# 1_Power.net
KiCad netlist of a schematic drawn in Altium Designer
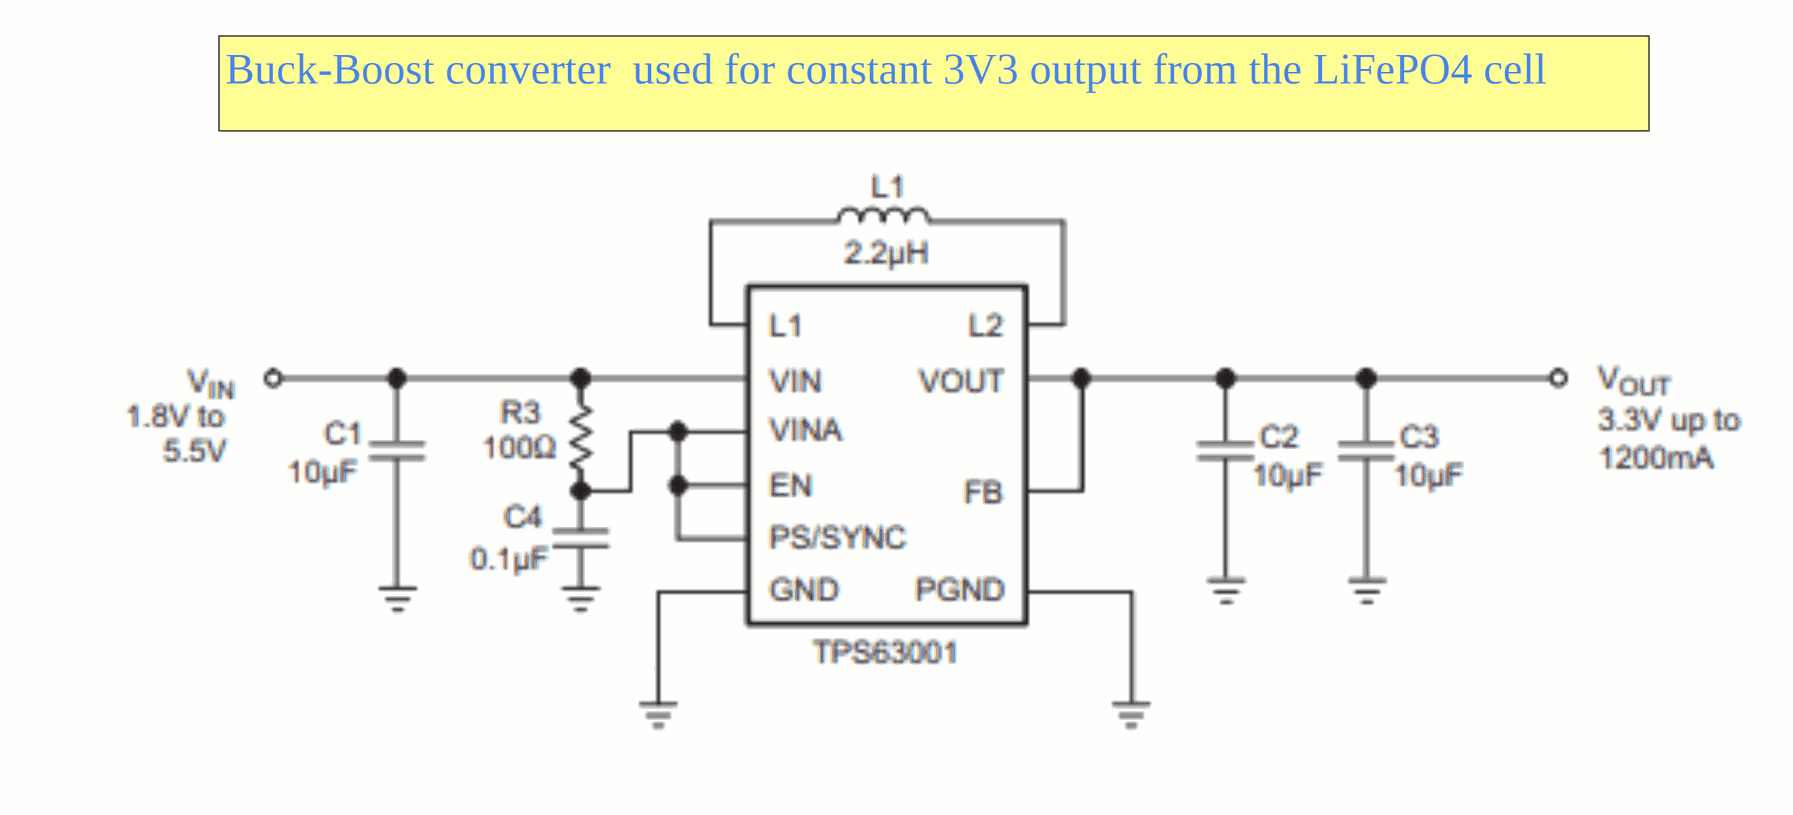
[diagram p0: 1_Power.SchDoc, top left]
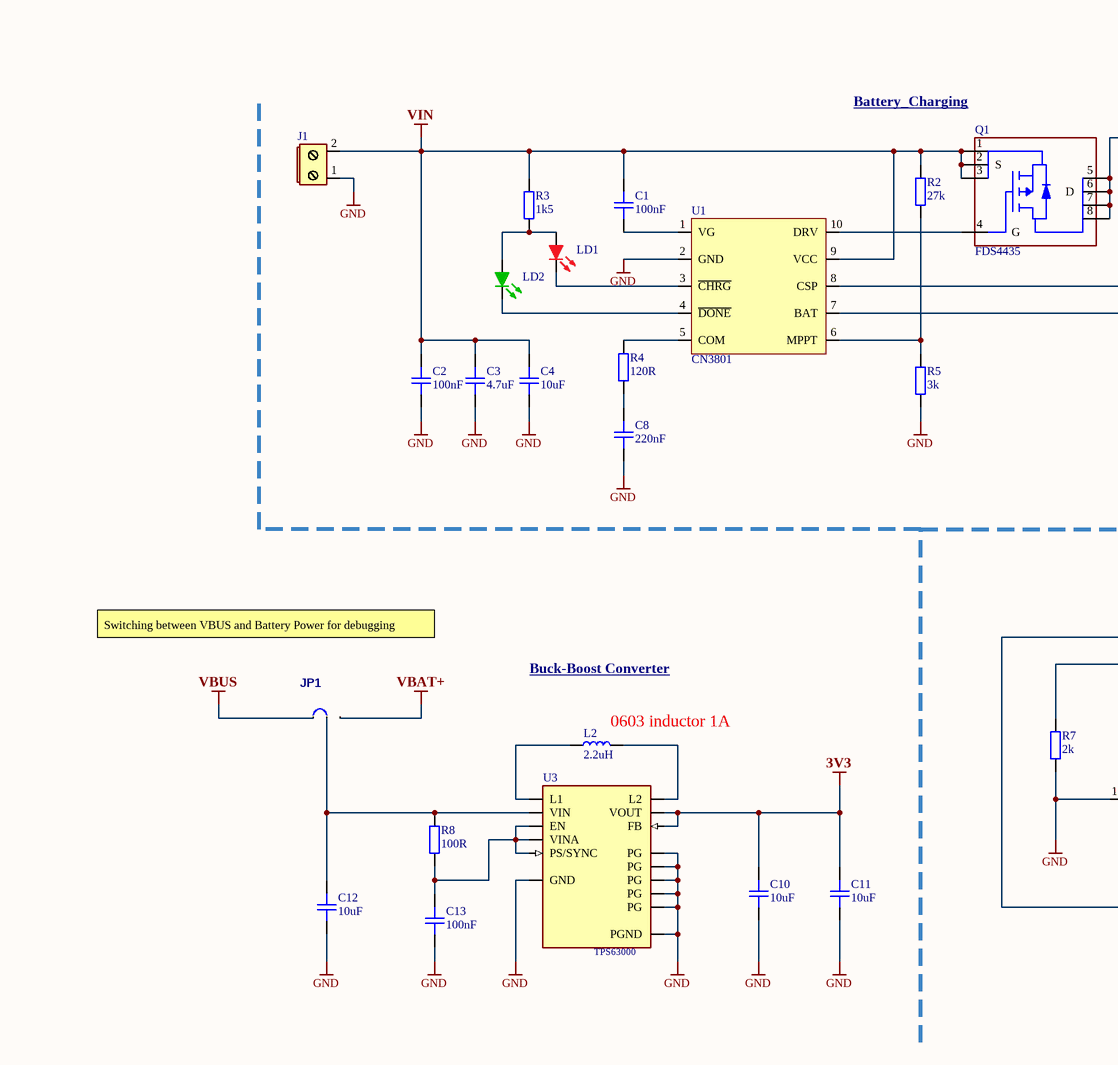
[diagram p1: 1_Power.SchDoc, top middle]
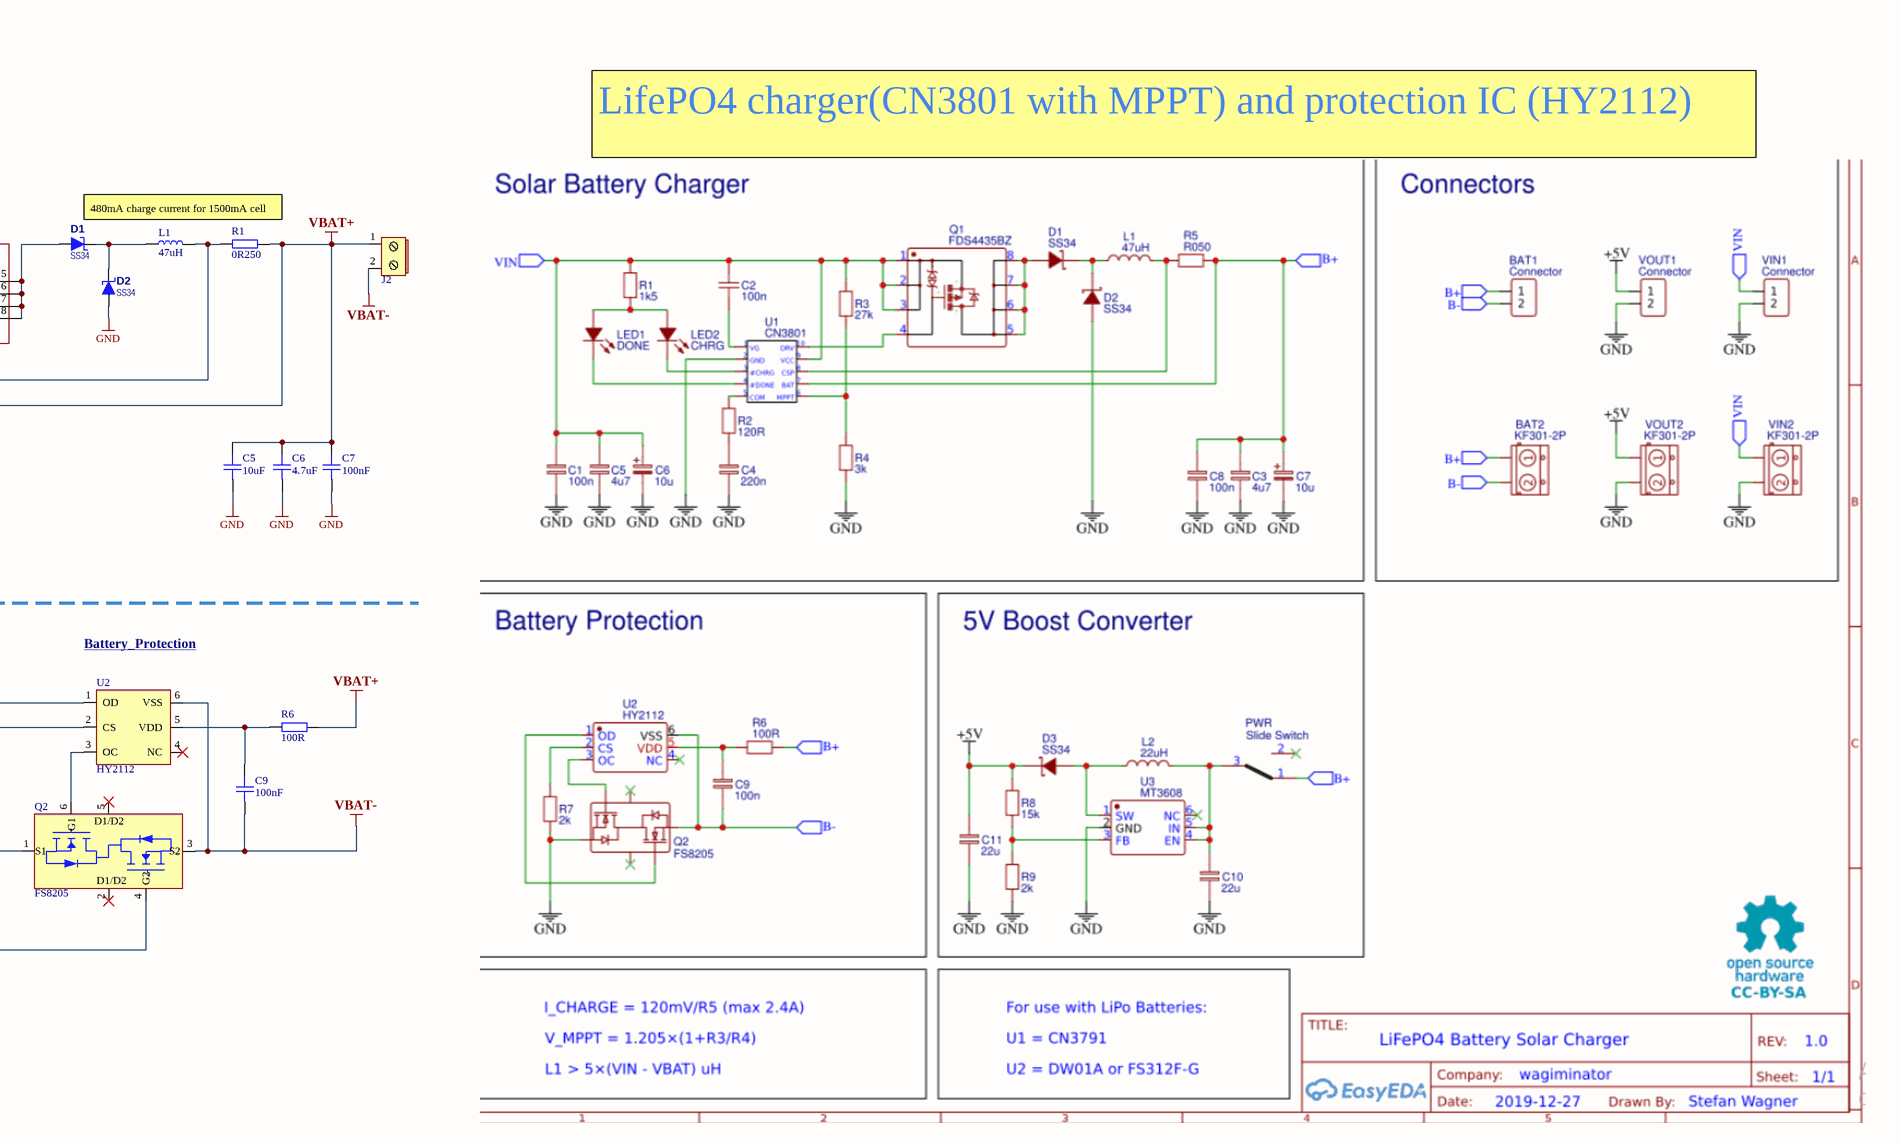
[diagram p2: 1_Power.SchDoc, top right]
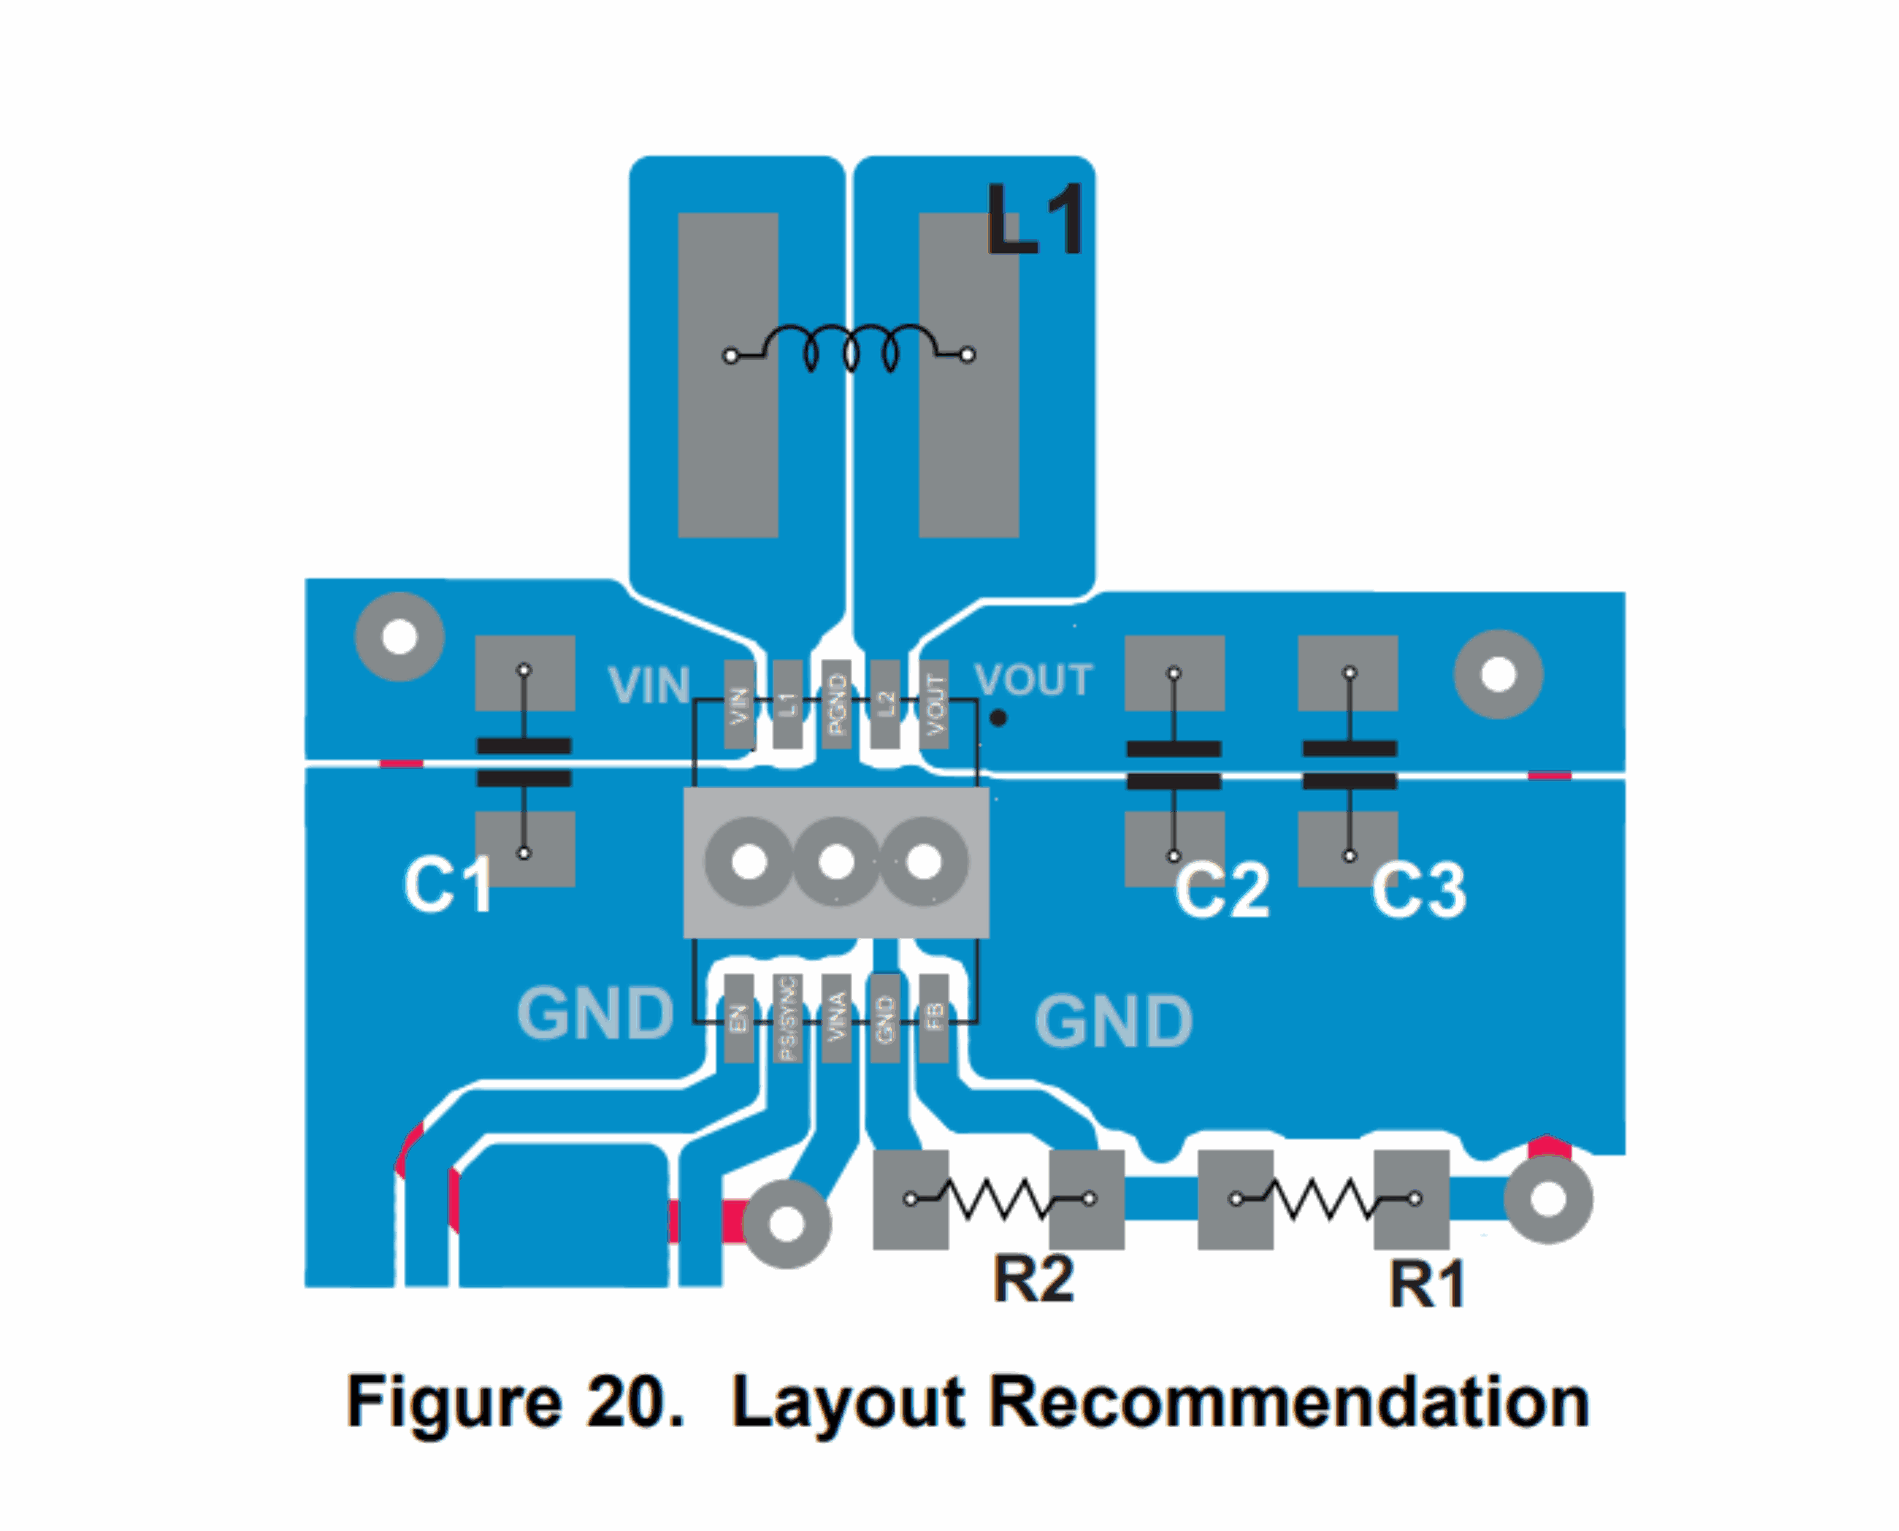
[diagram p3: 1_Power.SchDoc, bottom left]

(export (version "E")
  (design (tool "Eeschema 10.0.6"))
  (components
    (comp (ref "C1")
      (value "100nF")
      (footprint "C0603")
      (description "Capacitor SMD 0603")
      (libsource (lib "Schlib1") (part "CAP_0603"))
    )
    (comp (ref "C2")
      (value "100nF")
      (footprint "C0603")
      (description "Capacitor SMD 0603")
      (libsource (lib "Schlib1") (part "CAP_0603"))
    )
    (comp (ref "C3")
      (value "4.7uF")
      (footprint "C0603")
      (description "Capacitor SMD 0603")
      (libsource (lib "Schlib1") (part "CAP_0603"))
    )
    (comp (ref "C4")
      (value "10uF")
      (footprint "C0805")
      (description "Capacitor SMD 0805")
      (libsource (lib "Schlib1") (part "CAP_0805"))
    )
    (comp (ref "C5")
      (value "10uF")
      (footprint "C0805")
      (description "Capacitor SMD 0805")
      (libsource (lib "Schlib1") (part "CAP_0805"))
    )
    (comp (ref "C6")
      (value "4.7uF")
      (footprint "C0603")
      (description "Capacitor SMD 0603")
      (libsource (lib "Schlib1") (part "CAP_0603"))
    )
    (comp (ref "C7")
      (value "100nF")
      (footprint "C0603")
      (description "Capacitor SMD 0603")
      (libsource (lib "Schlib1") (part "CAP_0603"))
    )
    (comp (ref "C8")
      (value "220nF")
      (footprint "C0603")
      (description "Capacitor SMD 0603")
      (libsource (lib "Schlib1") (part "CAP_0603"))
    )
    (comp (ref "C9")
      (value "100nF")
      (footprint "C0603")
      (description "Capacitor SMD 0603")
      (libsource (lib "Schlib1") (part "CAP_0603"))
    )
    (comp (ref "C10")
      (value "10uF")
      (footprint "C0805")
      (description "Capacitor SMD 0805")
      (libsource (lib "Schlib1") (part "CAP_0805"))
    )
    (comp (ref "C11")
      (value "10uF")
      (footprint "C0805")
      (description "Capacitor SMD 0805")
      (libsource (lib "Schlib1") (part "CAP_0805"))
    )
    (comp (ref "C12")
      (value "10uF")
      (footprint "C0805")
      (description "Capacitor SMD 0805")
      (libsource (lib "Schlib1") (part "CAP_0805"))
    )
    (comp (ref "C13")
      (value "100nF")
      (footprint "C0603")
      (description "Capacitor SMD 0603")
      (libsource (lib "Schlib1") (part "CAP_0603"))
    )
    (comp (ref "D1")
      (value "SS34")
      (footprint "DO-214AC")
      (description "Diode")
      (libsource (lib "Schlib1") (part "DIODE_SCHOTTKY"))
    )
    (comp (ref "D2")
      (value "SS34")
      (footprint "DO-214AC")
      (description "Diode")
      (libsource (lib "Schlib1") (part "DIODE_SCHOTTKY"))
    )
    (comp (ref "J1")
      (value "PLUGIN_TERMINAL")
      (footprint "2.54_pluggable_terminal")
      (description "Screw terminal or plug terminal for power")
      (libsource (lib "") (part "Power_Connector_1"))
    )
    (comp (ref "J2")
      (value "PLUGIN_TERMINAL")
      (footprint "HEADER_1x2_2.54")
      (description "Screw terminal or plug terminal for power")
      (libsource (lib "Schlib1") (part "Power_Connector"))
    )
    (comp (ref "JP1")
      (value "JUMPER_3PIN")
      (footprint "HEADER_1x3_2.54")
      (libsource (lib "Schlib1") (part "JUMPER_3PIN"))
    )
    (comp (ref "L1")
      (value "47uH")
      (footprint "IND_5_7")
      (description "Inductor SMD 0603")
      (libsource (lib "Schlib1") (part "IND_0603"))
    )
    (comp (ref "L2")
      (value "2.2uH")
      (footprint "L0603")
      (description "Inductor SMD 1008")
      (libsource (lib "Schlib1") (part "IND_1008"))
    )
    (comp (ref "LD1")
      (value "LED_RED")
      (footprint "LED0603RD")
      (description "Typical BLUE SiC LED")
      (fields (field (name "PUBLISHER") "Altium Limited"))
      (libsource (lib "Schlib1") (part "LED_RED"))
    )
    (comp (ref "LD2")
      (value "LED_GREEN")
      (footprint "LED0603GR")
      (description "Typical BLUE SiC LED")
      (fields (field (name "PUBLISHER") "Altium Limited"))
      (libsource (lib "Schlib1") (part "LED_GREEN"))
    )
    (comp (ref "Q1") (value "FDS4435") (footprint "SOIC-SN8_N") (libsource (lib "Schlib1") (part "FDS4435")))
    (comp (ref "Q2") (value "FS8205") (footprint "SOT23-6") (libsource (lib "Schlib1") (part "FS8205")))
    (comp (ref "R1")
      (value "0R250")
      (footprint "R2512")
      (description "Resistor SMD 0805")
      (libsource (lib "Schlib1") (part "RES_0805"))
    )
    (comp (ref "R2")
      (value "27k")
      (footprint "R0603")
      (description "Resistor SMD 0603")
      (libsource (lib "Schlib1") (part "RES_0603"))
    )
    (comp (ref "R3")
      (value "1k5")
      (footprint "R0603")
      (description "Resistor SMD 0603")
      (libsource (lib "Schlib1") (part "RES_0603"))
    )
    (comp (ref "R4")
      (value "120R")
      (footprint "R0603")
      (description "Resistor SMD 0603")
      (libsource (lib "Schlib1") (part "RES_0603"))
    )
    (comp (ref "R5")
      (value "3k")
      (footprint "R0603")
      (description "Resistor SMD 0603")
      (libsource (lib "Schlib1") (part "RES_0603"))
    )
    (comp (ref "R6")
      (value "100R")
      (footprint "R0603")
      (description "Resistor SMD 0603")
      (libsource (lib "Schlib1") (part "RES_0603"))
    )
    (comp (ref "R7")
      (value "2k")
      (footprint "R0603")
      (description "Resistor SMD 0603")
      (libsource (lib "Schlib1") (part "RES_0603_1"))
    )
    (comp (ref "R8")
      (value "100R")
      (footprint "R0603")
      (description "Resistor SMD 0603")
      (libsource (lib "Schlib1") (part "RES_0603"))
    )
    (comp (ref "U1") (value "CN3801") (footprint "SSOP-10") (libsource (lib "Schlib1") (part "CN3801")))
    (comp (ref "U2")
      (value "HY2112")
      (footprint "SOT23-6")
      (description "LiFePO4 protection IC")
      (libsource (lib "Schlib1") (part "HY2112"))
    )
    (comp (ref "U3")
      (value "TPS63000")
      (footprint "VREG_V62/16624-01YE")
      (fields (field (name "MF") "Texas Instruments"))
      (libsource (lib "Schlib1") (part "TPS63000"))
    )
  )
  (nets
    (net (code "1") (name "3V3") (class "Default")
      (node (ref "C10") (pin "2") (pinfunction "2_2") (pintype "passive"))
      (node (ref "C11") (pin "2") (pinfunction "2_2") (pintype "passive"))
      (node (ref "U3") (pin "1") (pinfunction "VOUT_1") (pintype "power_in"))
      (node (ref "U3") (pin "10") (pinfunction "FB_10") (pintype "input"))
    )
    (net (code "2") (name "GND") (class "Default")
      (node (ref "C10") (pin "1") (pinfunction "1_1") (pintype "passive"))
      (node (ref "C11") (pin "1") (pinfunction "1_1") (pintype "passive"))
      (node (ref "C12") (pin "1") (pinfunction "1_1") (pintype "passive"))
      (node (ref "C13") (pin "1") (pinfunction "1_1") (pintype "passive"))
      (node (ref "C2") (pin "1") (pinfunction "1_1") (pintype "passive"))
      (node (ref "C3") (pin "1") (pinfunction "1_1") (pintype "passive"))
      (node (ref "C4") (pin "1") (pinfunction "1_1") (pintype "passive"))
      (node (ref "C5") (pin "1") (pinfunction "1_1") (pintype "passive"))
      (node (ref "C6") (pin "1") (pinfunction "1_1") (pintype "passive"))
      (node (ref "C7") (pin "1") (pinfunction "1_1") (pintype "passive"))
      (node (ref "C8") (pin "1") (pinfunction "1_1") (pintype "passive"))
      (node (ref "D2") (pin "1") (pinfunction "A_1") (pintype "passive"))
      (node (ref "J1") (pin "1") (pinfunction "1_1") (pintype "passive"))
      (node (ref "Q2") (pin "1") (pinfunction "S1_1") (pintype "passive"))
      (node (ref "R5") (pin "1") (pinfunction "1_1") (pintype "passive"))
      (node (ref "R7") (pin "1") (pinfunction "1_1") (pintype "passive"))
      (node (ref "U1") (pin "2") (pinfunction "GND_2") (pintype "passive"))
      (node (ref "U3") (pin "11") (pinfunction "PG_11") (pintype "power_in"))
      (node (ref "U3") (pin "3") (pinfunction "PGND_3") (pintype "power_in"))
      (node (ref "U3") (pin "9") (pinfunction "GND_9") (pintype "power_in"))
    )
    (net (code "3") (name "Net-(C8-Pad2)") (class "Default")
      (node (ref "C8") (pin "2") (pinfunction "2_2") (pintype "passive"))
      (node (ref "R4") (pin "1") (pinfunction "1_1") (pintype "passive"))
    )
    (net (code "4") (name "Net-(D1-A)") (class "Default")
      (node (ref "D1") (pin "1") (pinfunction "A_1") (pintype "passive"))
      (node (ref "Q1") (pin "5") (pinfunction "D_5") (pintype "passive"))
      (node (ref "Q1") (pin "6") (pinfunction "D_6") (pintype "passive"))
      (node (ref "Q1") (pin "7") (pinfunction "D_7") (pintype "passive"))
      (node (ref "Q1") (pin "8") (pinfunction "D_8") (pintype "passive"))
    )
    (net (code "5") (name "Net-(D1-K)") (class "Default")
      (node (ref "D1") (pin "2") (pinfunction "K_2") (pintype "passive"))
      (node (ref "D2") (pin "2") (pinfunction "K_2") (pintype "passive"))
      (node (ref "L1") (pin "1") (pinfunction "1_1") (pintype "passive"))
    )
    (net (code "6") (name "Net-(LD1-A)") (class "Default")
      (node (ref "LD1") (pin "1") (pinfunction "A_1") (pintype "passive"))
      (node (ref "LD2") (pin "1") (pinfunction "A_1") (pintype "passive"))
      (node (ref "R3") (pin "1") (pinfunction "1_1") (pintype "passive"))
    )
    (net (code "7") (name "Net-(LD1-K)") (class "Default")
      (node (ref "LD1") (pin "2") (pinfunction "K_2") (pintype "passive"))
      (node (ref "U1") (pin "3") (pinfunction "CHRG_3") (pintype "passive"))
    )
    (net (code "8") (name "Net-(LD2-K)") (class "Default")
      (node (ref "LD2") (pin "2") (pinfunction "K_2") (pintype "passive"))
      (node (ref "U1") (pin "4") (pinfunction "DONE_4") (pintype "passive"))
    )
    (net (code "9") (name "Net-(Q1-G)") (class "Default")
      (node (ref "Q1") (pin "4") (pinfunction "G_4") (pintype "passive"))
      (node (ref "U1") (pin "10") (pinfunction "DRV_10") (pintype "passive"))
    )
    (net (code "10") (name "Net-(Q2-G1)") (class "Default")
      (node (ref "Q2") (pin "6") (pinfunction "G1_6") (pintype "passive"))
      (node (ref "U2") (pin "3") (pinfunction "OC_3") (pintype "passive"))
    )
    (net (code "11") (name "Net-(Q2-G2)") (class "Default")
      (node (ref "Q2") (pin "4") (pinfunction "G2_4") (pintype "passive"))
      (node (ref "U2") (pin "1") (pinfunction "OD_1") (pintype "passive"))
    )
    (net (code "12") (name "Net-(U1-COM)") (class "Default")
      (node (ref "R4") (pin "2") (pinfunction "2_2") (pintype "passive"))
      (node (ref "U1") (pin "5") (pinfunction "COM_5") (pintype "passive"))
    )
    (net (code "13") (name "Net-(U1-CSP)") (class "Default")
      (node (ref "L1") (pin "2") (pinfunction "2_2") (pintype "passive"))
      (node (ref "R1") (pin "1") (pinfunction "1_1") (pintype "passive"))
      (node (ref "U1") (pin "8") (pinfunction "CSP_8") (pintype "passive"))
    )
    (net (code "14") (name "Net-(U1-MPPT)") (class "Default")
      (node (ref "R2") (pin "1") (pinfunction "1_1") (pintype "passive"))
      (node (ref "R5") (pin "2") (pinfunction "2_2") (pintype "passive"))
      (node (ref "U1") (pin "6") (pinfunction "MPPT_6") (pintype "passive"))
    )
    (net (code "15") (name "Net-(U1-VG)") (class "Default")
      (node (ref "C1") (pin "1") (pinfunction "1_1") (pintype "passive"))
      (node (ref "U1") (pin "1") (pinfunction "VG_1") (pintype "passive"))
    )
    (net (code "16") (name "Net-(U2-CS)") (class "Default")
      (node (ref "R7") (pin "2") (pinfunction "2_2") (pintype "passive"))
      (node (ref "U2") (pin "2") (pinfunction "CS_2") (pintype "passive"))
    )
    (net (code "17") (name "Net-(U2-VDD)") (class "Default")
      (node (ref "C9") (pin "2") (pinfunction "2_2") (pintype "passive"))
      (node (ref "R6") (pin "2") (pinfunction "2_2") (pintype "passive"))
      (node (ref "U2") (pin "5") (pinfunction "VDD_5") (pintype "passive"))
    )
    (net (code "18") (name "Net-(U3-EN)") (class "Default")
      (node (ref "C13") (pin "2") (pinfunction "2_2") (pintype "passive"))
      (node (ref "R8") (pin "1") (pinfunction "1_1") (pintype "passive"))
      (node (ref "U3") (pin "6") (pinfunction "EN_6") (pintype "bidirectional"))
      (node (ref "U3") (pin "7") (pinfunction "PS/SYNC_7") (pintype "input"))
      (node (ref "U3") (pin "8") (pinfunction "VINA_8") (pintype "power_in"))
    )
    (net (code "19") (name "Net-(U3-L1)") (class "Default")
      (node (ref "L2") (pin "1") (pinfunction "1_1") (pintype "passive"))
      (node (ref "U3") (pin "4") (pinfunction "L1_4") (pintype "passive"))
    )
    (net (code "20") (name "Net-(U3-L2)") (class "Default")
      (node (ref "L2") (pin "2") (pinfunction "2_2") (pintype "passive"))
      (node (ref "U3") (pin "2") (pinfunction "L2_2") (pintype "passive"))
    )
    (net (code "21") (name "Net-(U3-VIN)") (class "Default")
      (node (ref "C12") (pin "2") (pinfunction "2_2") (pintype "passive"))
      (node (ref "JP1") (pin "2") (pinfunction "2_2") (pintype "passive"))
      (node (ref "R8") (pin "2") (pinfunction "2_2") (pintype "passive"))
      (node (ref "U3") (pin "5") (pinfunction "VIN_5") (pintype "power_in"))
    )
    (net (code "22") (name "VBAT+") (class "Default")
      (node (ref "C5") (pin "2") (pinfunction "2_2") (pintype "passive"))
      (node (ref "C6") (pin "2") (pinfunction "2_2") (pintype "passive"))
      (node (ref "C7") (pin "2") (pinfunction "2_2") (pintype "passive"))
      (node (ref "J2") (pin "1") (pinfunction "1_1") (pintype "passive"))
      (node (ref "JP1") (pin "3") (pinfunction "3_3") (pintype "passive"))
      (node (ref "R1") (pin "2") (pinfunction "2_2") (pintype "passive"))
      (node (ref "R6") (pin "1") (pinfunction "1_1") (pintype "passive"))
      (node (ref "U1") (pin "7") (pinfunction "BAT_7") (pintype "passive"))
    )
    (net (code "23") (name "VBAT-") (class "Default")
      (node (ref "C9") (pin "1") (pinfunction "1_1") (pintype "passive"))
      (node (ref "J2") (pin "2") (pinfunction "2_2") (pintype "passive"))
      (node (ref "Q2") (pin "3") (pinfunction "S2_3") (pintype "passive"))
      (node (ref "U2") (pin "6") (pinfunction "VSS_6") (pintype "passive"))
    )
    (net (code "24") (name "VBUS") (class "Default")
      (node (ref "JP1") (pin "1") (pinfunction "1_1") (pintype "passive"))
    )
    (net (code "25") (name "VIN") (class "Default")
      (node (ref "C1") (pin "2") (pinfunction "2_2") (pintype "passive"))
      (node (ref "C2") (pin "2") (pinfunction "2_2") (pintype "passive"))
      (node (ref "C3") (pin "2") (pinfunction "2_2") (pintype "passive"))
      (node (ref "C4") (pin "2") (pinfunction "2_2") (pintype "passive"))
      (node (ref "J1") (pin "2") (pinfunction "2_2") (pintype "passive"))
      (node (ref "Q1") (pin "1") (pinfunction "S_1") (pintype "passive"))
      (node (ref "Q1") (pin "2") (pinfunction "S_2") (pintype "passive"))
      (node (ref "Q1") (pin "3") (pinfunction "S_3") (pintype "passive"))
      (node (ref "R2") (pin "2") (pinfunction "2_2") (pintype "passive"))
      (node (ref "R3") (pin "2") (pinfunction "2_2") (pintype "passive"))
      (node (ref "U1") (pin "9") (pinfunction "VCC_9") (pintype "passive"))
    )
    (net (code "26") (name "unconnected-(Q2-D1{slash}D2-Pad2)") (class "Default")
      (node (ref "Q2") (pin "2") (pinfunction "D1/D2_2") (pintype "passive+no_connect"))
    )
    (net (code "27") (name "unconnected-(Q2-D1{slash}D2-Pad5)") (class "Default")
      (node (ref "Q2") (pin "5") (pinfunction "D1/D2_5") (pintype "passive+no_connect"))
    )
    (net (code "28") (name "unconnected-(U2-NC-Pad4)") (class "Default")
      (node (ref "U2") (pin "4") (pinfunction "NC_4") (pintype "passive+no_connect"))
    )
  )
)
